# Supply_0.net
KiCad netlist of a schematic drawn in Altium Designer
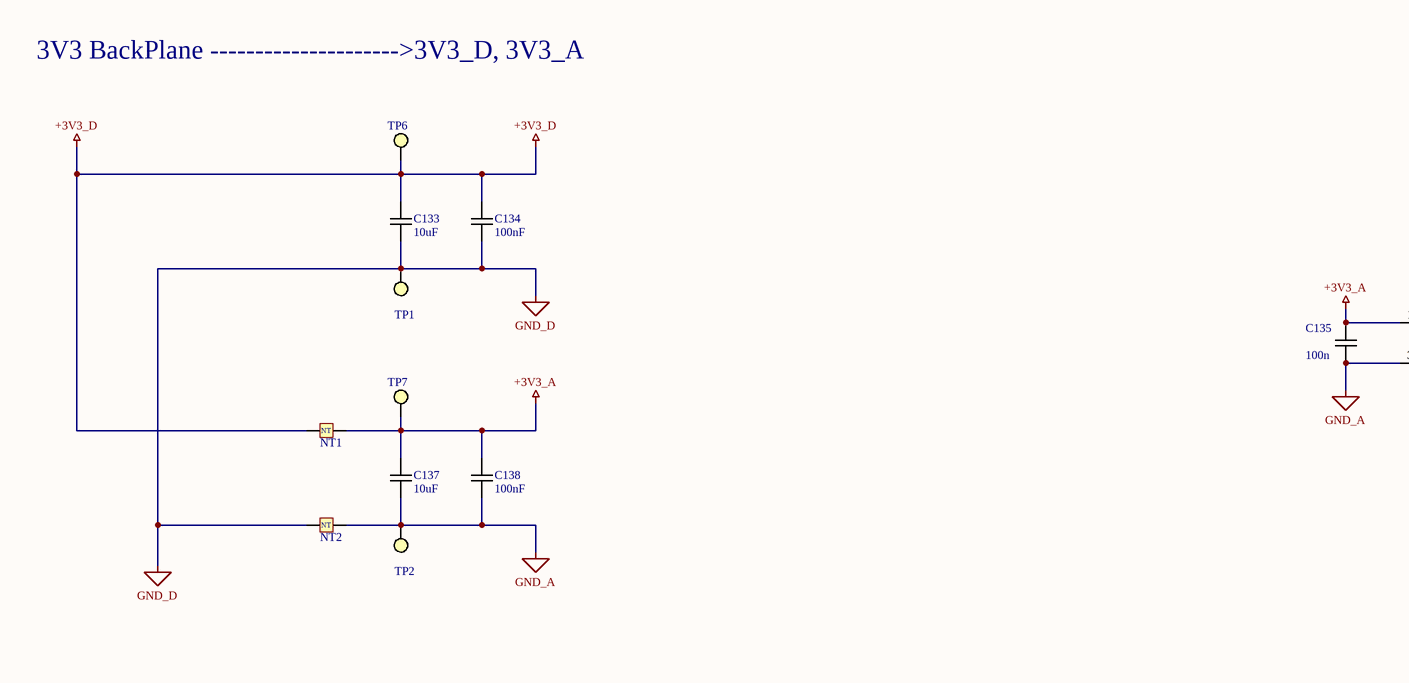
[diagram p0: Supply_0.SchDoc, left]
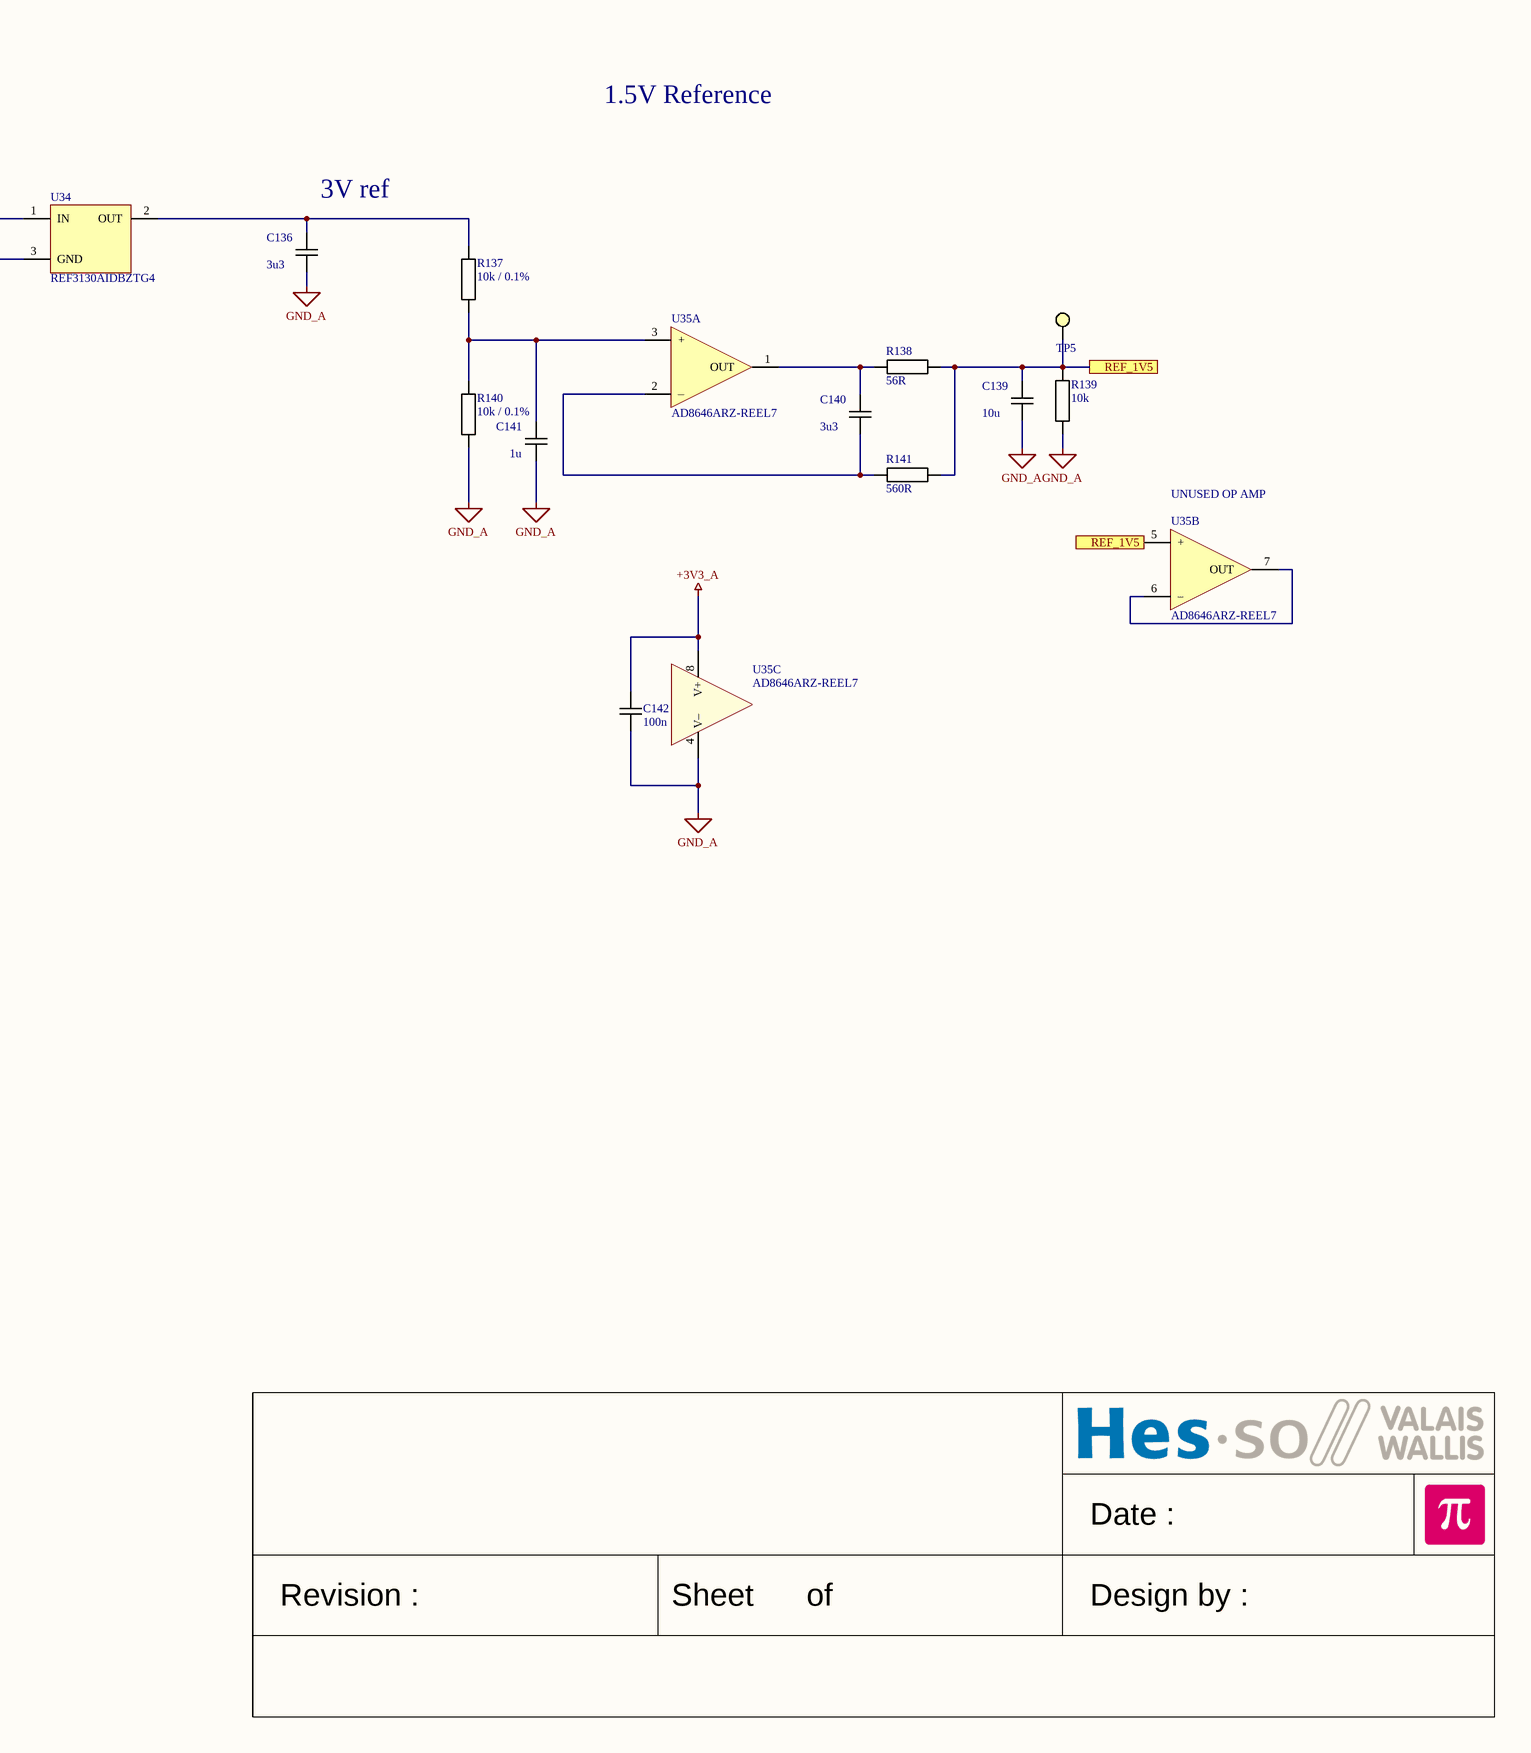
[diagram p1: Supply_0.SchDoc, right]

(export (version "E")
  (design (tool "Eeschema 10.0.6"))
  (components
    (comp (ref "C133")
      (value "10uF")
      (footprint "CAPACITOR 2012 REFLOW")
      (description "Capacitor X7R 10% 10V 2012(0805)")
      (libsource (lib "Capacitor") (part "Capacitor"))
    )
    (comp (ref "C134")
      (value "100nF")
      (footprint "CAPACITOR 2012 REFLOW")
      (description "Capacitor X7R 10% 50V 2012(0805)")
      (libsource (lib "Capacitor") (part "Capacitor"))
    )
    (comp (ref "C135")
      (value "100n")
      (footprint "CAPACITOR 1608 REFLOW")
      (description "Capacitor X7R 10% 50V 1608(0603)")
      (libsource (lib "Capacitor") (part "Capacitor"))
    )
    (comp (ref "C136")
      (value "3u3")
      (footprint "CAPACITOR 2012 REFLOW")
      (description "Capacitor X7R 10% 10V 2012(0805)")
      (libsource (lib "Capacitor") (part "Capacitor"))
    )
    (comp (ref "C137")
      (value "10uF")
      (footprint "CAPACITOR 2012 REFLOW")
      (description "Capacitor X7R 10% 10V 2012(0805)")
      (libsource (lib "Capacitor") (part "Capacitor"))
    )
    (comp (ref "C138")
      (value "100nF")
      (footprint "CAPACITOR 2012 REFLOW")
      (description "Capacitor X7R 10% 50V 2012(0805)")
      (libsource (lib "Capacitor") (part "Capacitor"))
    )
    (comp (ref "C139")
      (value "10u")
      (footprint "CAPACITOR 2012 REFLOW")
      (description "Capacitor X7R 10% 10V 2012(0805)")
      (libsource (lib "Capacitor") (part "Capacitor"))
    )
    (comp (ref "C140")
      (value "3u3")
      (footprint "CAPACITOR 2012 REFLOW")
      (description "Capacitor X7R 10% 10V 2012(0805)")
      (libsource (lib "Capacitor") (part "Capacitor"))
    )
    (comp (ref "C141")
      (value "1u")
      (footprint "CAPACITOR 2012 REFLOW")
      (description "Capacitor X7R 10% 10V 2012(0805)")
      (libsource (lib "Capacitor") (part "Capacitor"))
    )
    (comp (ref "C142")
      (value "100n")
      (footprint "CAPACITOR 1608 REFLOW")
      (description "Capacitor X7R 10% 50V 1608(0603)")
      (libsource (lib "Capacitor") (part "Capacitor"))
    )
    (comp (ref "NT1")
      (value "Net Tie")
      (footprint "NET TIE 1005")
      (description "Connection for 2 different NETNAME")
      (libsource (lib "Jumper") (part "Net Tie"))
    )
    (comp (ref "NT2")
      (value "Net Tie")
      (footprint "NET TIE 1005")
      (description "Connection for 2 different NETNAME")
      (libsource (lib "Jumper") (part "Net Tie"))
    )
    (comp (ref "R137")
      (value "10k / 0.1%")
      (footprint "RESISTOR 1608 REFLOW")
      (description "Resistor 1% 50V 100mW 1608(0603)")
      (libsource (lib "Resistor") (part "Resistor"))
    )
    (comp (ref "R138")
      (value "56R")
      (footprint "RESISTOR 1608 REFLOW")
      (description "Resistor 1% 50V 100mW 1608(0603)")
      (libsource (lib "Resistor") (part "Resistor"))
    )
    (comp (ref "R139")
      (value "10k")
      (footprint "RESISTOR 1608 REFLOW")
      (description "Resistor 1% 50V 100mW 1608(0603)")
      (libsource (lib "Resistor") (part "Resistor"))
    )
    (comp (ref "R140")
      (value "10k / 0.1%")
      (footprint "RESISTOR 1608 REFLOW")
      (description "Resistor 1% 50V 100mW 1608(0603)")
      (libsource (lib "Resistor") (part "Resistor"))
    )
    (comp (ref "R141")
      (value "560R")
      (footprint "RESISTOR 1608 REFLOW")
      (description "Resistor 1% 50V 100mW 1608(0603)")
      (libsource (lib "Resistor") (part "Resistor"))
    )
    (comp (ref "TP1")
      (value "*")
      (footprint "Test Point Keystone Miniature BLACK")
      (description "Test Point")
      (libsource (lib "Testpoint") (part "Test Point"))
    )
    (comp (ref "TP2")
      (value "*")
      (footprint "Test Point Keystone Miniature BLACK")
      (description "Test Point")
      (libsource (lib "Testpoint") (part "Test Point"))
    )
    (comp (ref "TP5")
      (value "*")
      (footprint "Test Point Keystone Miniature RED")
      (description "Test Point")
      (libsource (lib "Testpoint") (part "Test Point"))
    )
    (comp (ref "TP6")
      (value "*")
      (footprint "Test Point Keystone Miniature BLACK")
      (description "Test Point")
      (libsource (lib "Testpoint") (part "Test Point"))
    )
    (comp (ref "TP7")
      (value "*")
      (footprint "Test Point Keystone Miniature BLACK")
      (description "Test Point")
      (libsource (lib "Testpoint") (part "Test Point"))
    )
    (comp (ref "U34")
      (value "REF3130AIDBZTG4")
      (footprint "SOT23 P0.95 C1.6x3.0 H1.3")
      (description "Generic Positive Voltage Reference")
      (libsource (lib "Regulator") (part "REFERENCE SOT23 IN,OUT,GND"))
    )
    (comp (ref "U35")
      (value "AD8646ARZ-REEL7")
      (footprint "SO8 P1.27 C4.0X5.0 H1.75")
      (description "Generic dual OPA 8 pins")
      (fields (field (name "MANUFACTURER") "Analog Devices"))
      (libsource (lib "Amplifier") (part "OPA DUAL"))
    )
  )
  (nets
    (net (code "1") (name "+3V3_A") (class "Default")
      (node (ref "C135") (pin "2") (pinfunction "2_2") (pintype "passive"))
      (node (ref "C137") (pin "1") (pinfunction "1_1") (pintype "passive"))
      (node (ref "C138") (pin "1") (pinfunction "1_1") (pintype "passive"))
      (node (ref "C142") (pin "2") (pinfunction "2_2") (pintype "passive"))
      (node (ref "NT1") (pin "2") (pinfunction "2_2") (pintype "passive"))
      (node (ref "TP7") (pin "1") (pinfunction "1_1") (pintype "passive"))
      (node (ref "U34") (pin "1") (pinfunction "IN_1") (pintype "passive"))
      (node (ref "U35") (pin "8") (pinfunction "V+_8") (pintype "passive"))
    )
    (net (code "2") (name "+3V3_D") (class "Default")
      (node (ref "C133") (pin "1") (pinfunction "1_1") (pintype "passive"))
      (node (ref "C134") (pin "1") (pinfunction "1_1") (pintype "passive"))
      (node (ref "NT1") (pin "1") (pinfunction "1_1") (pintype "passive"))
      (node (ref "TP6") (pin "1") (pinfunction "1_1") (pintype "passive"))
    )
    (net (code "3") (name "/REF_1V5") (class "Default")
      (node (ref "C139") (pin "2") (pinfunction "2_2") (pintype "passive"))
      (node (ref "R138") (pin "1") (pinfunction "1_1") (pintype "passive"))
      (node (ref "R139") (pin "1") (pinfunction "1_1") (pintype "passive"))
      (node (ref "R141") (pin "1") (pinfunction "1_1") (pintype "passive"))
      (node (ref "TP5") (pin "1") (pinfunction "1_1") (pintype "passive"))
      (node (ref "U35") (pin "5") (pinfunction "+_5") (pintype "passive"))
    )
    (net (code "4") (name "GND_A") (class "Default")
      (node (ref "C135") (pin "1") (pinfunction "1_1") (pintype "passive"))
      (node (ref "C136") (pin "1") (pinfunction "1_1") (pintype "passive"))
      (node (ref "C137") (pin "2") (pinfunction "2_2") (pintype "passive"))
      (node (ref "C138") (pin "2") (pinfunction "2_2") (pintype "passive"))
      (node (ref "C139") (pin "1") (pinfunction "1_1") (pintype "passive"))
      (node (ref "C141") (pin "1") (pinfunction "1_1") (pintype "passive"))
      (node (ref "C142") (pin "1") (pinfunction "1_1") (pintype "passive"))
      (node (ref "NT2") (pin "2") (pinfunction "2_2") (pintype "passive"))
      (node (ref "R139") (pin "2") (pinfunction "2_2") (pintype "passive"))
      (node (ref "R140") (pin "2") (pinfunction "2_2") (pintype "passive"))
      (node (ref "TP2") (pin "1") (pinfunction "1_1") (pintype "passive"))
      (node (ref "U34") (pin "3") (pinfunction "GND_3") (pintype "passive"))
      (node (ref "U35") (pin "4") (pinfunction "V–_4") (pintype "passive"))
    )
    (net (code "5") (name "GND_D") (class "Default")
      (node (ref "C133") (pin "2") (pinfunction "2_2") (pintype "passive"))
      (node (ref "C134") (pin "2") (pinfunction "2_2") (pintype "passive"))
      (node (ref "NT2") (pin "1") (pinfunction "1_1") (pintype "passive"))
      (node (ref "TP1") (pin "1") (pinfunction "1_1") (pintype "passive"))
    )
    (net (code "6") (name "Net-(U34-OUT)") (class "Default")
      (node (ref "C136") (pin "2") (pinfunction "2_2") (pintype "passive"))
      (node (ref "R137") (pin "2") (pinfunction "2_2") (pintype "passive"))
      (node (ref "U34") (pin "2") (pinfunction "OUT_2") (pintype "passive"))
    )
    (net (code "7") (name "Net-(U35A-+)") (class "Default")
      (node (ref "C141") (pin "2") (pinfunction "2_2") (pintype "passive"))
      (node (ref "R137") (pin "1") (pinfunction "1_1") (pintype "passive"))
      (node (ref "R140") (pin "1") (pinfunction "1_1") (pintype "passive"))
      (node (ref "U35") (pin "3") (pinfunction "+_3") (pintype "passive"))
    )
    (net (code "8") (name "Net-(U35A-OUT)") (class "Default")
      (node (ref "C140") (pin "2") (pinfunction "2_2") (pintype "passive"))
      (node (ref "R138") (pin "2") (pinfunction "2_2") (pintype "passive"))
      (node (ref "U35") (pin "1") (pinfunction "OUT_1") (pintype "passive"))
    )
    (net (code "9") (name "Net-(U35A-–)") (class "Default")
      (node (ref "C140") (pin "1") (pinfunction "1_1") (pintype "passive"))
      (node (ref "R141") (pin "2") (pinfunction "2_2") (pintype "passive"))
      (node (ref "U35") (pin "2") (pinfunction "–_2") (pintype "passive"))
    )
    (net (code "10") (name "Net-(U35B-OUT)") (class "Default")
      (node (ref "U35") (pin "6") (pinfunction "–_6") (pintype "passive"))
      (node (ref "U35") (pin "7") (pinfunction "OUT_7") (pintype "passive"))
    )
  )
)
